# schematic_easyEDA.net
KiCad netlist of a schematic drawn in EasyEDA
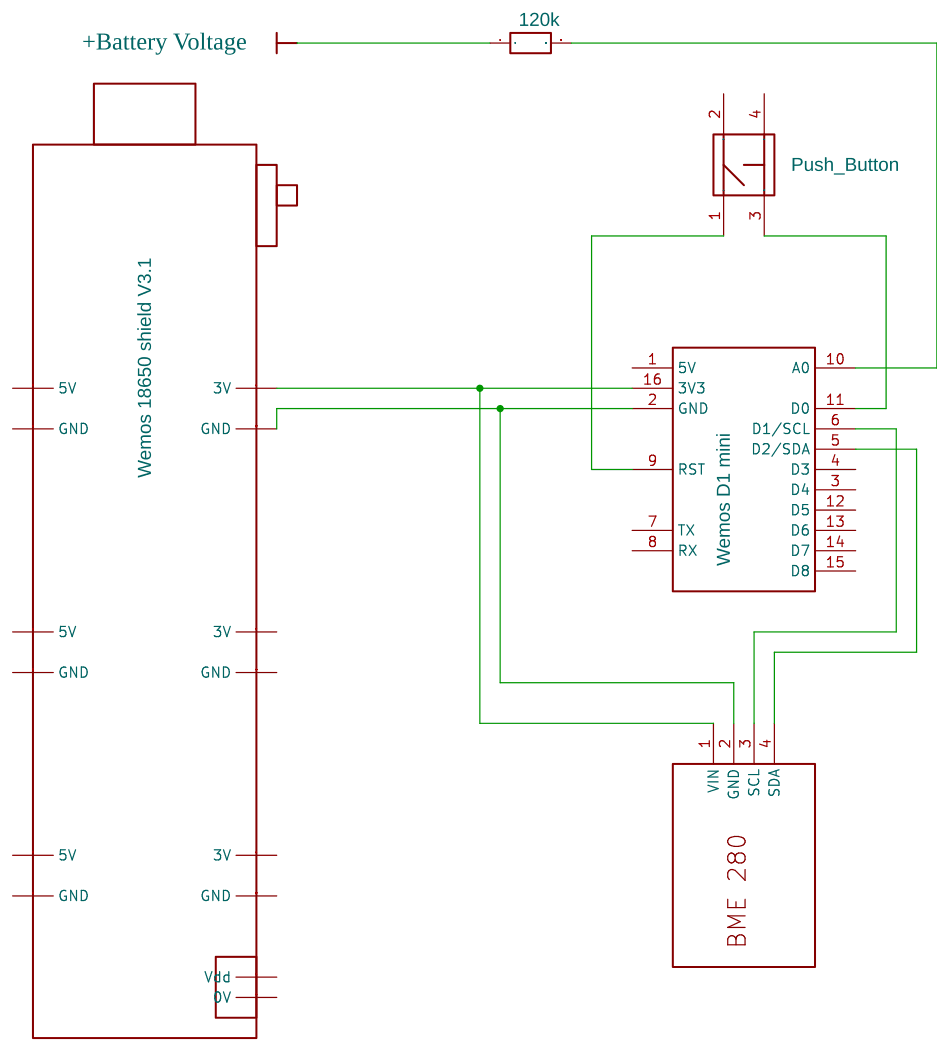
[diagram p0: schematic sheet]

(export (version "E")
  (design (tool "Eeschema 10.0.6"))
  (components
    (comp (ref "R1") (value "120k") (libsource (lib "") (part "R_0805_EU")))
    (comp (ref "U1") (value "BME 280") (libsource (lib "") (part "BME 280")))
    (comp (ref "U2")
      (value "Wemos 18650 shield V3.1")
      (fields (field (name "BOM_Manufacturer Part") "Wemos 18650 shield"))
      (libsource (lib "") (part "Wemos 18650 shield V3.1"))
    )
    (comp (ref "U3") (value "Wemos D1 mini") (libsource (lib "") (part "Wemos D1 mini")))
    (comp (ref "U4")
      (value "Push_Button")
      (fields (field (name "BOM_Manufacturer Part") "Push_Button_NO"))
      (libsource (lib "") (part "Push_Button"))
    )
  )
  (nets
    (net (code "1") (name "+Battery Voltage") (class "Default")
      (node (ref "R1") (pin "1") (pinfunction "1_1") (pintype "unspecified"))
    )
    (net (code "2") (name "Net-(U1-GND)") (class "Default")
      (node (ref "U1") (pin "2") (pinfunction "GND_2") (pintype "unspecified"))
      (node (ref "U2") (pin "GND") (pinfunction "GND_GND") (pintype "unspecified"))
      (node (ref "U3") (pin "2") (pinfunction "GND_2") (pintype "unspecified"))
    )
    (net (code "3") (name "Net-(U1-SCL)") (class "Default")
      (node (ref "U1") (pin "3") (pinfunction "SCL_3") (pintype "unspecified"))
      (node (ref "U3") (pin "6") (pinfunction "D1/SCL_6") (pintype "unspecified"))
    )
    (net (code "4") (name "Net-(U1-SDA)") (class "Default")
      (node (ref "U1") (pin "4") (pinfunction "SDA_4") (pintype "unspecified"))
      (node (ref "U3") (pin "5") (pinfunction "D2/SDA_5") (pintype "unspecified"))
    )
    (net (code "5") (name "Net-(U1-VIN)") (class "Default")
      (node (ref "U1") (pin "1") (pinfunction "VIN_1") (pintype "unspecified"))
      (node (ref "U2") (pin "5V") (pinfunction "3V_5V") (pintype "unspecified"))
      (node (ref "U3") (pin "16") (pinfunction "3V3_16") (pintype "unspecified"))
    )
    (net (code "6") (name "Net-(U3-A0)") (class "Default")
      (node (ref "R1") (pin "2") (pinfunction "2_2") (pintype "unspecified"))
      (node (ref "U3") (pin "10") (pinfunction "A0_10") (pintype "unspecified"))
    )
    (net (code "7") (name "Net-(U3-D0)") (class "Default")
      (node (ref "U3") (pin "11") (pinfunction "D0_11") (pintype "unspecified"))
      (node (ref "U4") (pin "3") (pinfunction "3_3") (pintype "unspecified"))
    )
    (net (code "8") (name "Net-(U3-RST)") (class "Default")
      (node (ref "U3") (pin "9") (pinfunction "RST_9") (pintype "unspecified"))
      (node (ref "U4") (pin "1") (pinfunction "1_1") (pintype "unspecified"))
    )
    (net (code "9") (name "unconnected-(U2-0V-Pad13)") (class "Default")
      (node (ref "U2") (pin "13") (pinfunction "0V_13") (pintype "unspecified"))
    )
    (net (code "10") (name "unconnected-(U2-3V-Pad5V)") (class "Default")
      (node (ref "U2") (pin "5V") (pinfunction "3V_5V") (pintype "unspecified"))
    )
    (net (code "11") (name "unconnected-(U2-3V-Pad5V)_1") (class "Default")
      (node (ref "U2") (pin "5V") (pinfunction "3V_5V") (pintype "unspecified"))
    )
    (net (code "12") (name "unconnected-(U2-5V-Pad3V)") (class "Default")
      (node (ref "U2") (pin "3V") (pinfunction "5V_3V") (pintype "unspecified"))
    )
    (net (code "13") (name "unconnected-(U2-5V-Pad3V)_1") (class "Default")
      (node (ref "U2") (pin "3V") (pinfunction "5V_3V") (pintype "unspecified"))
    )
    (net (code "14") (name "unconnected-(U2-5V-Pad3V)_2") (class "Default")
      (node (ref "U2") (pin "3V") (pinfunction "5V_3V") (pintype "unspecified"))
    )
    (net (code "15") (name "unconnected-(U2-PadGND)") (class "Default")
      (node (ref "U2") (pin "GND") (pinfunction "GND_GND") (pintype "unspecified"))
    )
    (net (code "16") (name "unconnected-(U2-PadGND)_1") (class "Default")
      (node (ref "U2") (pin "GND") (pinfunction "GND_GND") (pintype "unspecified"))
    )
    (net (code "17") (name "unconnected-(U2-PadGND)_2") (class "Default")
      (node (ref "U2") (pin "GND") (pinfunction "GND_GND") (pintype "unspecified"))
    )
    (net (code "18") (name "unconnected-(U2-PadGND)_3") (class "Default")
      (node (ref "U2") (pin "GND") (pinfunction "GND_GND") (pintype "unspecified"))
    )
    (net (code "19") (name "unconnected-(U2-PadGND)_4") (class "Default")
      (node (ref "U2") (pin "GND") (pinfunction "GND_GND") (pintype "unspecified"))
    )
    (net (code "20") (name "unconnected-(U2-Vdd-Pad14)") (class "Default")
      (node (ref "U2") (pin "14") (pinfunction "Vdd_14") (pintype "unspecified"))
    )
    (net (code "21") (name "unconnected-(U3-5V-Pad1)") (class "Default")
      (node (ref "U3") (pin "1") (pinfunction "5V_1") (pintype "unspecified"))
    )
    (net (code "22") (name "unconnected-(U3-D3-Pad4)") (class "Default")
      (node (ref "U3") (pin "4") (pinfunction "D3_4") (pintype "unspecified"))
    )
    (net (code "23") (name "unconnected-(U3-D4-Pad3)") (class "Default")
      (node (ref "U3") (pin "3") (pinfunction "D4_3") (pintype "unspecified"))
    )
    (net (code "24") (name "unconnected-(U3-D5-Pad12)") (class "Default")
      (node (ref "U3") (pin "12") (pinfunction "D5_12") (pintype "unspecified"))
    )
    (net (code "25") (name "unconnected-(U3-D6-Pad13)") (class "Default")
      (node (ref "U3") (pin "13") (pinfunction "D6_13") (pintype "unspecified"))
    )
    (net (code "26") (name "unconnected-(U3-D7-Pad14)") (class "Default")
      (node (ref "U3") (pin "14") (pinfunction "D7_14") (pintype "unspecified"))
    )
    (net (code "27") (name "unconnected-(U3-D8-Pad15)") (class "Default")
      (node (ref "U3") (pin "15") (pinfunction "D8_15") (pintype "unspecified"))
    )
    (net (code "28") (name "unconnected-(U3-RX-Pad8)") (class "Default")
      (node (ref "U3") (pin "8") (pinfunction "RX_8") (pintype "unspecified"))
    )
    (net (code "29") (name "unconnected-(U3-TX-Pad7)") (class "Default")
      (node (ref "U3") (pin "7") (pinfunction "TX_7") (pintype "unspecified"))
    )
    (net (code "30") (name "unconnected-(U4-Pad2)") (class "Default")
      (node (ref "U4") (pin "2") (pinfunction "2_2") (pintype "unspecified"))
    )
    (net (code "31") (name "unconnected-(U4-Pad4)") (class "Default")
      (node (ref "U4") (pin "4") (pinfunction "4_4") (pintype "unspecified"))
    )
  )
)
